# STM32f407.net
KiCad netlist of a schematic drawn in Altium Designer
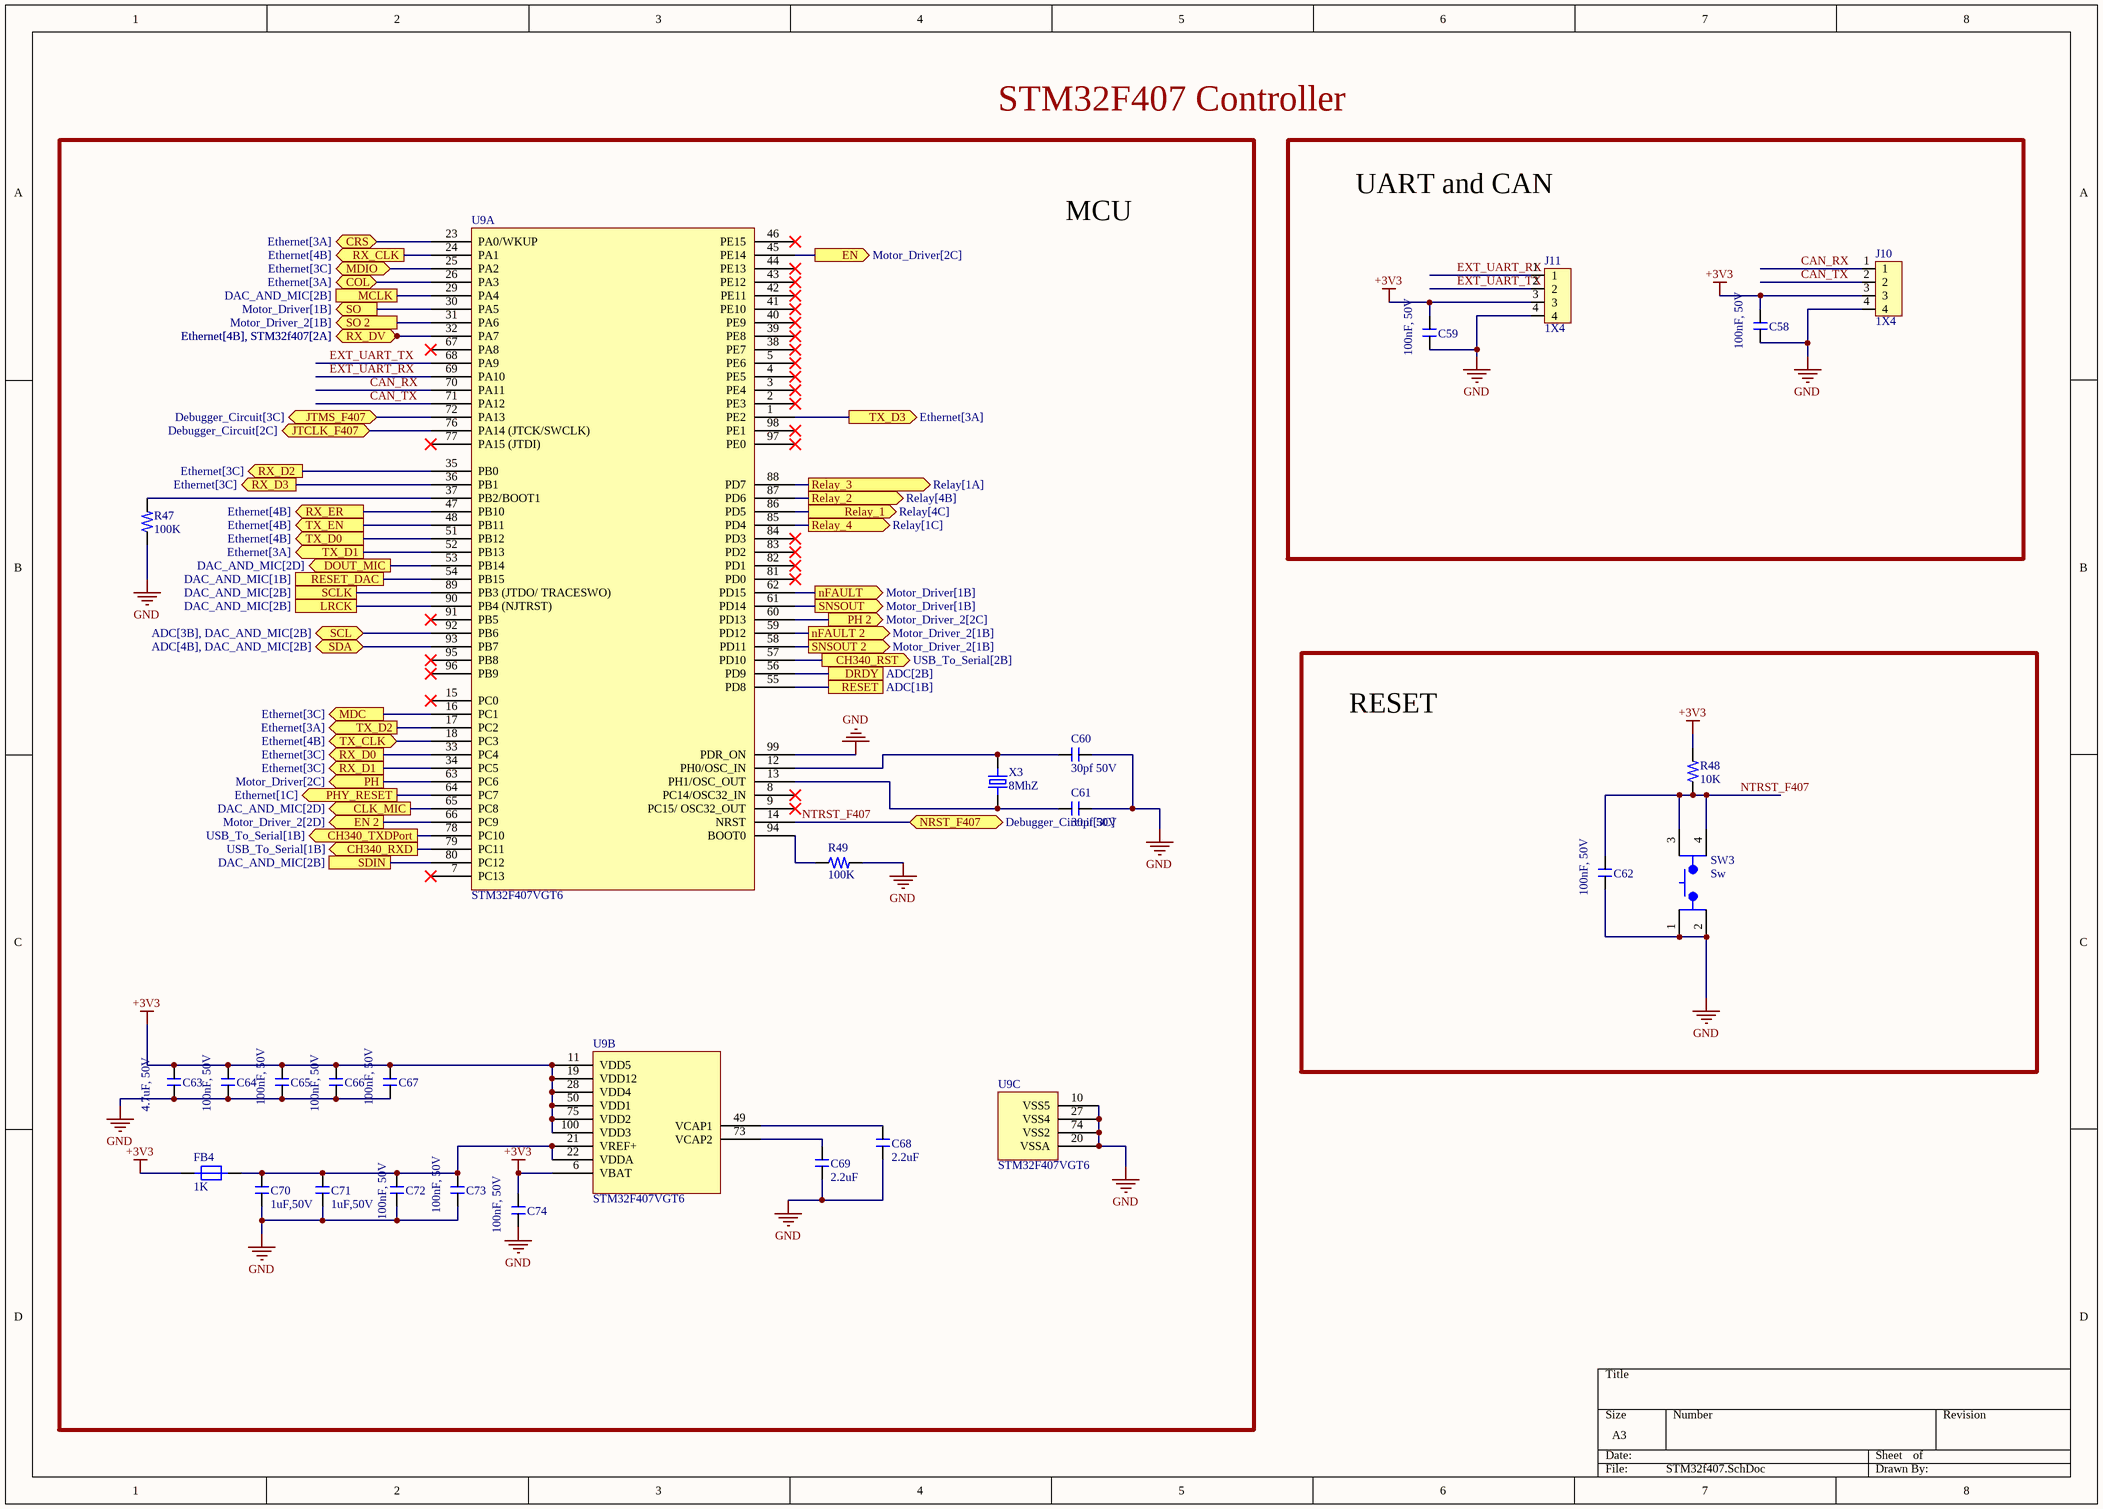
[diagram p0: STM32f407.SchDoc]

(export (version "E")
  (design (tool "Eeschema 10.0.6"))
  (components
    (comp (ref "C58")
      (value "100nF, 50V")
      (footprint "Capacitor_0805")
      (description "Multilayer Ceramic Capacitor, 0.1 uF, 50 V, ï¿½ 10%, X7R, 0805 [2012 Metric]")
      (fields
        (field (name "MANUFACTURER") "Samsung")
        (field (name "MANUFACTURER PART NUMBER") "CL21B104KBCNNNC")
      )
      (libsource (lib "Schematics_Library_Hanif") (part "Cap_100nF_0805"))
    )
    (comp (ref "C59")
      (value "100nF, 50V")
      (footprint "Capacitor_0805")
      (description "Multilayer Ceramic Capacitor, 0.1 uF, 50 V, ï¿½ 10%, X7R, 0805 [2012 Metric]")
      (fields
        (field (name "MANUFACTURER") "Samsung")
        (field (name "MANUFACTURER PART NUMBER") "CL21B104KBCNNNC")
      )
      (libsource (lib "Schematics_Library_Hanif") (part "Cap_100nF_0805"))
    )
    (comp (ref "C60")
      (value "30pf 50V")
      (footprint "Capacitor_0805")
      (fields
        (field (name "MANUFACTURER") "KEMET")
        (field (name "MANUFACTURER PART NUMBER") "C0805C300K5GACTU")
      )
      (libsource (lib "Schematics_Library_Hanif") (part "Cap_30pf_0805"))
    )
    (comp (ref "C61")
      (value "30pf 50V")
      (footprint "Capacitor_0805")
      (fields
        (field (name "MANUFACTURER") "KEMET")
        (field (name "MANUFACTURER PART NUMBER") "C0805C300K5GACTU")
      )
      (libsource (lib "Schematics_Library_Hanif") (part "Cap_30pf_0805"))
    )
    (comp (ref "C62")
      (value "100nF, 50V")
      (footprint "Capacitor_0805")
      (description "Multilayer Ceramic Capacitor, 0.1 uF, 50 V, ï¿½ 10%, X7R, 0805 [2012 Metric]")
      (fields
        (field (name "MANUFACTURER") "Samsung")
        (field (name "MANUFACTURER PART NUMBER") "CL21B104KBCNNNC")
      )
      (libsource (lib "Schematics_Library_Hanif") (part "Cap_100nF_0805"))
    )
    (comp (ref "C63")
      (value "4.7uF, 50V")
      (footprint "Capacitor_0805")
      (description "Multilayer Ceramic Capacitor, 4.7 uF, 50 V, ï¿½ 10%, X5R, 0805 [2012 Metric]")
      (fields
        (field (name "MANUFACTURER") "Murata")
        (field (name "MANUFACTURER PART NUMBER") "GRM21BR61H475KE51L")
      )
      (libsource (lib "Schematics_Library_Hanif") (part "Cap_4.7uF_0805"))
    )
    (comp (ref "C64")
      (value "100nF, 50V")
      (footprint "Capacitor_0805")
      (description "Multilayer Ceramic Capacitor, 0.1 uF, 50 V, ï¿½ 10%, X7R, 0805 [2012 Metric]")
      (fields
        (field (name "MANUFACTURER") "Samsung")
        (field (name "MANUFACTURER PART NUMBER") "CL21B104KBCNNNC")
      )
      (libsource (lib "Schematics_Library_Hanif") (part "Cap_100nF_0805"))
    )
    (comp (ref "C65")
      (value "100nF, 50V")
      (footprint "Capacitor_0805")
      (description "Multilayer Ceramic Capacitor, 0.1 uF, 50 V, ï¿½ 10%, X7R, 0805 [2012 Metric]")
      (fields
        (field (name "MANUFACTURER") "Samsung")
        (field (name "MANUFACTURER PART NUMBER") "CL21B104KBCNNNC")
      )
      (libsource (lib "Schematics_Library_Hanif") (part "Cap_100nF_0805"))
    )
    (comp (ref "C66")
      (value "100nF, 50V")
      (footprint "Capacitor_0805")
      (description "Multilayer Ceramic Capacitor, 0.1 uF, 50 V, ï¿½ 10%, X7R, 0805 [2012 Metric]")
      (fields
        (field (name "MANUFACTURER") "Samsung")
        (field (name "MANUFACTURER PART NUMBER") "CL21B104KBCNNNC")
      )
      (libsource (lib "Schematics_Library_Hanif") (part "Cap_100nF_0805"))
    )
    (comp (ref "C67")
      (value "100nF, 50V")
      (footprint "Capacitor_0805")
      (description "Multilayer Ceramic Capacitor, 0.1 uF, 50 V, ï¿½ 10%, X7R, 0805 [2012 Metric]")
      (fields
        (field (name "MANUFACTURER") "Samsung")
        (field (name "MANUFACTURER PART NUMBER") "CL21B104KBCNNNC")
      )
      (libsource (lib "Schematics_Library_Hanif") (part "Cap_100nF_0805"))
    )
    (comp (ref "C68")
      (value "2.2uF")
      (footprint "Capacitor_0805")
      (description "Multilayer Ceramic Capacitor, 2.2 uF, 25 V, ± 10%, X7R, 0805 [2012 Metric]")
      (fields
        (field (name "MANUFACTURER") "Samsung")
        (field (name "MANUFACTURER PART NUMBER") "CL21B225KAFNFNE")
      )
      (libsource (lib "Schematics_Library_Hanif") (part "CAP_2.2uF_0805"))
    )
    (comp (ref "C69")
      (value "2.2uF")
      (footprint "Capacitor_0805")
      (description "Multilayer Ceramic Capacitor, 2.2 uF, 25 V, ± 10%, X7R, 0805 [2012 Metric]")
      (fields
        (field (name "MANUFACTURER") "Samsung")
        (field (name "MANUFACTURER PART NUMBER") "CL21B225KAFNFNE")
      )
      (libsource (lib "Schematics_Library_Hanif") (part "CAP_2.2uF_0805"))
    )
    (comp (ref "C70")
      (value "1uF,50V")
      (footprint "Capacitor_0805")
      (description "0805 1 uF 50 V ±5 % Tolerance X7R Surface Mount Multilayer Ceramic Capacitor")
      (fields
        (field (name "MANUFACTURER") "Yageo")
        (field (name "MANUFACTURER PART NUMBER") "CC0805JKX7R9BB105")
      )
      (libsource (lib "Schematics_Library_Hanif") (part "Cap_1uF_0805"))
    )
    (comp (ref "C71")
      (value "1uF,50V")
      (footprint "Capacitor_0805")
      (description "0805 1 uF 50 V ±5 % Tolerance X7R Surface Mount Multilayer Ceramic Capacitor")
      (fields
        (field (name "MANUFACTURER") "Yageo")
        (field (name "MANUFACTURER PART NUMBER") "CC0805JKX7R9BB105")
      )
      (libsource (lib "Schematics_Library_Hanif") (part "Cap_1uF_0805"))
    )
    (comp (ref "C72")
      (value "100nF, 50V")
      (footprint "Capacitor_0805")
      (description "Multilayer Ceramic Capacitor, 0.1 uF, 50 V, ï¿½ 10%, X7R, 0805 [2012 Metric]")
      (fields
        (field (name "MANUFACTURER") "Samsung")
        (field (name "MANUFACTURER PART NUMBER") "CL21B104KBCNNNC")
      )
      (libsource (lib "Schematics_Library_Hanif") (part "Cap_100nF_0805"))
    )
    (comp (ref "C73")
      (value "100nF, 50V")
      (footprint "Capacitor_0805")
      (description "Multilayer Ceramic Capacitor, 0.1 uF, 50 V, ï¿½ 10%, X7R, 0805 [2012 Metric]")
      (fields
        (field (name "MANUFACTURER") "Samsung")
        (field (name "MANUFACTURER PART NUMBER") "CL21B104KBCNNNC")
      )
      (libsource (lib "Schematics_Library_Hanif") (part "Cap_100nF_0805"))
    )
    (comp (ref "C74")
      (value "100nF, 50V")
      (footprint "Capacitor_0805")
      (description "Multilayer Ceramic Capacitor, 0.1 uF, 50 V, ï¿½ 10%, X7R, 0805 [2012 Metric]")
      (fields
        (field (name "MANUFACTURER") "Samsung")
        (field (name "MANUFACTURER PART NUMBER") "CL21B104KBCNNNC")
      )
      (libsource (lib "Schematics_Library_Hanif") (part "Cap_100nF_0805"))
    )
    (comp (ref "FB4")
      (value "1K")
      (footprint "FB_0805")
      (description "Ferrite Beads Multi-Layer High Current 1KOhm 25% 100MHz 1.6A 0.12Ohm DCR 0805 Automotive T/R")
      (fields
        (field (name "MANUFACTURER") "Murata")
        (field (name "MANUFACTURER PART NUMBER") "BLM21SP102SH1D")
      )
      (libsource (lib "Schematics_Library_Hanif") (part "FB_BLM21SP102SH1D"))
    )
    (comp (ref "J10")
      (value "1X4")
      (footprint "Header_1X4_2.54mm")
      (description "THT Vertical Pin Header WR-PHD, Pitch 2.54 mm, Single Row, 4 pins")
      (fields
        (field (name "MANUFACTURER") "Wurth Electronics")
        (field (name "MANUFACTURER PART NUMBER") "61300411121")
      )
      (libsource (lib "Schematics_Library_Hanif") (part "Header_Male_1X4_2.54"))
    )
    (comp (ref "J11")
      (value "1X4")
      (footprint "Header_1X4_2.54mm")
      (description "THT Vertical Pin Header WR-PHD, Pitch 2.54 mm, Single Row, 4 pins")
      (fields
        (field (name "MANUFACTURER") "Wurth Electronics")
        (field (name "MANUFACTURER PART NUMBER") "61300411121")
      )
      (libsource (lib "Schematics_Library_Hanif") (part "Header_Male_1X4_2.54"))
    )
    (comp (ref "R47")
      (value "100K")
      (footprint "Resistor_0603")
      (description "Res Thick Film 0603 100K Ohm 1% 0.1W(1/10W) ±100ppm/C Pad SMD Automotive T/R")
      (fields
        (field (name "MANUFACTURER") "Stackpole Electronics")
        (field (name "MANUFACTURER PART NUMBER") "RMCF0603FT100K")
      )
      (libsource (lib "Schematics_Library_Hanif") (part "R_100K_0603"))
    )
    (comp (ref "R48")
      (value "10K")
      (footprint "Resistor_0603")
      (description "SMD Chip Resistor, 10 kOhm, ï¿½ 1%, 100 mW, 0603 [1608 Metric], Thick Film, General Purpose")
      (fields
        (field (name "MANUFACTURER") "Yageo")
        (field (name "MANUFACTURER PART NUMBER") "RC0603FR-0710KL")
      )
      (libsource (lib "Schematics_Library_Hanif") (part "R_10K_0603"))
    )
    (comp (ref "R49")
      (value "100K")
      (footprint "Resistor_0603")
      (description "Res Thick Film 0603 100K Ohm 1% 0.1W(1/10W) ±100ppm/C Pad SMD Automotive T/R")
      (fields
        (field (name "MANUFACTURER") "Stackpole Electronics")
        (field (name "MANUFACTURER PART NUMBER") "RMCF0603FT100K")
      )
      (libsource (lib "Schematics_Library_Hanif") (part "R_100K_0603"))
    )
    (comp (ref "SW3")
      (value "Sw")
      (footprint "SW_Tactile_SMD")
      (description "TL3305A Series SPST 12 V 4.5 x 4.5 mm 260 gf Top Actuated SMT Tactile Switch")
      (fields
        (field (name "MANUFACTURER") "E-Switch")
        (field (name "MANUFACTURER PART NUMBER") "TL3305AF260QG")
      )
      (libsource (lib "Schematics_Library_Hanif") (part "SW_Tactile_SPST"))
    )
    (comp (ref "U9")
      (value "STM32F407VGT6")
      (footprint "QFN100_19.6_669_58X10_SMD")
      (description "ARM® Cortex®-M4 STM32F4 Microcontroller IC 32-Bit 168MHz 1MB (1M x 8) FLASH 100-LQFP (14x14)")
      (fields (field (name "MANUFACTURER") "STMicroelectronics"))
      (libsource (lib "Schematics_Library_Hanif") (part "IC_STM32F407VGT6"))
    )
    (comp (ref "X3")
      (value "8MhZ")
      (footprint "XTAL_8MhZ")
      (description "Crystal 8MHz ±30ppm (Tol) ±50ppm (Stability) 32pF FUND 60Ohm 2-Pin HC-49/USX SMD T/R")
      (fields
        (field (name "MANUFACTURER") "ECS International")
        (field (name "MANUFACTURER PART NUMBER") "ECS-80-32-5PX-TR")
      )
      (libsource (lib "Schematics_Library_Hanif") (part "Xtal_8MHz"))
    )
  )
  (nets
    (net (code "1") (name "+3V3") (class "Default")
      (node (ref "C58") (pin "2") (pinfunction "2_2") (pintype "passive"))
      (node (ref "C59") (pin "2") (pinfunction "2_2") (pintype "passive"))
      (node (ref "C63") (pin "2") (pinfunction "2_2") (pintype "passive"))
      (node (ref "C64") (pin "2") (pinfunction "2_2") (pintype "passive"))
      (node (ref "C65") (pin "2") (pinfunction "2_2") (pintype "passive"))
      (node (ref "C66") (pin "2") (pinfunction "2_2") (pintype "passive"))
      (node (ref "C67") (pin "2") (pinfunction "2_2") (pintype "passive"))
      (node (ref "C74") (pin "2") (pinfunction "2_2") (pintype "passive"))
      (node (ref "FB4") (pin "1") (pinfunction "1_1") (pintype "passive"))
      (node (ref "J10") (pin "3") (pinfunction "3_3") (pintype "passive"))
      (node (ref "J11") (pin "3") (pinfunction "3_3") (pintype "passive"))
      (node (ref "R48") (pin "2") (pinfunction "2_2") (pintype "passive"))
      (node (ref "U9") (pin "100") (pinfunction "VDD3_100") (pintype "passive"))
      (node (ref "U9") (pin "11") (pinfunction "VDD5_11") (pintype "passive"))
      (node (ref "U9") (pin "19") (pinfunction "VDD12_19") (pintype "passive"))
      (node (ref "U9") (pin "28") (pinfunction "VDD4_28") (pintype "passive"))
      (node (ref "U9") (pin "50") (pinfunction "VDD1_50") (pintype "passive"))
      (node (ref "U9") (pin "6") (pinfunction "VBAT_6") (pintype "passive"))
      (node (ref "U9") (pin "75") (pinfunction "VDD2_75") (pintype "passive"))
    )
    (net (code "2") (name "/CAN_RX") (class "Default")
      (node (ref "J10") (pin "1") (pinfunction "1_1") (pintype "passive"))
      (node (ref "U9") (pin "70") (pinfunction "PA11_70") (pintype "passive"))
    )
    (net (code "3") (name "/CAN_TX") (class "Default")
      (node (ref "J10") (pin "2") (pinfunction "2_2") (pintype "passive"))
      (node (ref "U9") (pin "71") (pinfunction "PA12_71") (pintype "passive"))
    )
    (net (code "4") (name "/CH340_RST") (class "Default")
      (node (ref "U9") (pin "57") (pinfunction "PD10_57") (pintype "passive"))
    )
    (net (code "5") (name "/CH340_RXD") (class "Default")
      (node (ref "U9") (pin "79") (pinfunction "PC11_79") (pintype "passive"))
    )
    (net (code "6") (name "/CH340_TXDPort") (class "Default")
      (node (ref "U9") (pin "78") (pinfunction "PC10_78") (pintype "passive"))
    )
    (net (code "7") (name "/CLK_MIC") (class "Default")
      (node (ref "U9") (pin "65") (pinfunction "PC8_65") (pintype "passive"))
    )
    (net (code "8") (name "/COL") (class "Default")
      (node (ref "U9") (pin "26") (pinfunction "PA3_26") (pintype "passive"))
    )
    (net (code "9") (name "/CRS") (class "Default")
      (node (ref "U9") (pin "23") (pinfunction "PA0/WKUP_23") (pintype "passive"))
    )
    (net (code "10") (name "/DOUT_MIC") (class "Default")
      (node (ref "U9") (pin "53") (pinfunction "PB14_53") (pintype "passive"))
    )
    (net (code "11") (name "/DRDY") (class "Default")
      (node (ref "U9") (pin "56") (pinfunction "PD9_56") (pintype "passive"))
    )
    (net (code "12") (name "/EN") (class "Default")
      (node (ref "U9") (pin "45") (pinfunction "PE14_45") (pintype "passive"))
    )
    (net (code "13") (name "/EN 2") (class "Default")
      (node (ref "U9") (pin "66") (pinfunction "PC9_66") (pintype "passive"))
    )
    (net (code "14") (name "/EXT_UART_RX") (class "Default")
      (node (ref "J11") (pin "1") (pinfunction "1_1") (pintype "passive"))
      (node (ref "U9") (pin "69") (pinfunction "PA10_69") (pintype "passive"))
    )
    (net (code "15") (name "/EXT_UART_TX") (class "Default")
      (node (ref "J11") (pin "2") (pinfunction "2_2") (pintype "passive"))
      (node (ref "U9") (pin "68") (pinfunction "PA9_68") (pintype "passive"))
    )
    (net (code "16") (name "/JTCLK_F407") (class "Default")
      (node (ref "U9") (pin "76") (pinfunction "PA14_(JTCK/SWCLK)_76") (pintype "passive"))
    )
    (net (code "17") (name "/JTMS_F407") (class "Default")
      (node (ref "U9") (pin "72") (pinfunction "PA13_72") (pintype "passive"))
    )
    (net (code "18") (name "/LRCK") (class "Default")
      (node (ref "U9") (pin "90") (pinfunction "PB4_(NJTRST)_90") (pintype "passive"))
    )
    (net (code "19") (name "/MCLK") (class "Default")
      (node (ref "U9") (pin "29") (pinfunction "PA4_29") (pintype "passive"))
    )
    (net (code "20") (name "/MDC") (class "Default")
      (node (ref "U9") (pin "16") (pinfunction "PC1_16") (pintype "passive"))
    )
    (net (code "21") (name "/MDIO") (class "Default")
      (node (ref "U9") (pin "25") (pinfunction "PA2_25") (pintype "passive"))
    )
    (net (code "22") (name "/NTRST_F407") (class "Default")
      (node (ref "C62") (pin "2") (pinfunction "2_2") (pintype "passive"))
      (node (ref "R48") (pin "1") (pinfunction "1_1") (pintype "passive"))
      (node (ref "SW3") (pin "3") (pinfunction "3_3") (pintype "passive"))
      (node (ref "SW3") (pin "4") (pinfunction "4_4") (pintype "passive"))
      (node (ref "U9") (pin "14") (pinfunction "NRST_14") (pintype "passive"))
    )
    (net (code "23") (name "/PH") (class "Default")
      (node (ref "U9") (pin "63") (pinfunction "PC6_63") (pintype "passive"))
    )
    (net (code "24") (name "/PH 2") (class "Default")
      (node (ref "U9") (pin "60") (pinfunction "PD13_60") (pintype "passive"))
    )
    (net (code "25") (name "/PHY_RESET") (class "Default")
      (node (ref "U9") (pin "64") (pinfunction "PC7_64") (pintype "passive"))
    )
    (net (code "26") (name "/RESET") (class "Default")
      (node (ref "U9") (pin "55") (pinfunction "PD8_55") (pintype "passive"))
    )
    (net (code "27") (name "/RESET_DAC") (class "Default")
      (node (ref "U9") (pin "54") (pinfunction "PB15_54") (pintype "passive"))
    )
    (net (code "28") (name "/RX_CLK") (class "Default")
      (node (ref "U9") (pin "24") (pinfunction "PA1_24") (pintype "passive"))
    )
    (net (code "29") (name "/RX_D0") (class "Default")
      (node (ref "U9") (pin "33") (pinfunction "PC4_33") (pintype "passive"))
    )
    (net (code "30") (name "/RX_D1") (class "Default")
      (node (ref "U9") (pin "34") (pinfunction "PC5_34") (pintype "passive"))
    )
    (net (code "31") (name "/RX_D2") (class "Default")
      (node (ref "U9") (pin "35") (pinfunction "PB0_35") (pintype "passive"))
    )
    (net (code "32") (name "/RX_D3") (class "Default")
      (node (ref "U9") (pin "36") (pinfunction "PB1_36") (pintype "passive"))
    )
    (net (code "33") (name "/RX_DV") (class "Default")
      (node (ref "U9") (pin "32") (pinfunction "PA7_32") (pintype "passive"))
    )
    (net (code "34") (name "/RX_ER") (class "Default")
      (node (ref "U9") (pin "47") (pinfunction "PB10_47") (pintype "passive"))
    )
    (net (code "35") (name "/Relay_1") (class "Default")
      (node (ref "U9") (pin "86") (pinfunction "PD5_86") (pintype "passive"))
    )
    (net (code "36") (name "/Relay_2") (class "Default")
      (node (ref "U9") (pin "87") (pinfunction "PD6_87") (pintype "passive"))
    )
    (net (code "37") (name "/Relay_3") (class "Default")
      (node (ref "U9") (pin "88") (pinfunction "PD7_88") (pintype "passive"))
    )
    (net (code "38") (name "/Relay_4") (class "Default")
      (node (ref "U9") (pin "85") (pinfunction "PD4_85") (pintype "passive"))
    )
    (net (code "39") (name "/SCL") (class "Default")
      (node (ref "U9") (pin "92") (pinfunction "PB6_92") (pintype "passive"))
    )
    (net (code "40") (name "/SCLK") (class "Default")
      (node (ref "U9") (pin "89") (pinfunction "PB3_(JTDO/_TRACESWO)_89") (pintype "passive"))
    )
    (net (code "41") (name "/SDA") (class "Default")
      (node (ref "U9") (pin "93") (pinfunction "PB7_93") (pintype "passive"))
    )
    (net (code "42") (name "/SDIN") (class "Default")
      (node (ref "U9") (pin "80") (pinfunction "PC12_80") (pintype "passive"))
    )
    (net (code "43") (name "/SNSOUT") (class "Default")
      (node (ref "U9") (pin "61") (pinfunction "PD14_61") (pintype "passive"))
    )
    (net (code "44") (name "/SNSOUT 2") (class "Default")
      (node (ref "U9") (pin "58") (pinfunction "PD11_58") (pintype "passive"))
    )
    (net (code "45") (name "/SO") (class "Default")
      (node (ref "U9") (pin "30") (pinfunction "PA5_30") (pintype "passive"))
    )
    (net (code "46") (name "/SO 2") (class "Default")
      (node (ref "U9") (pin "31") (pinfunction "PA6_31") (pintype "passive"))
    )
    (net (code "47") (name "/TX_CLK") (class "Default")
      (node (ref "U9") (pin "18") (pinfunction "PC3_18") (pintype "passive"))
    )
    (net (code "48") (name "/TX_D0") (class "Default")
      (node (ref "U9") (pin "51") (pinfunction "PB12_51") (pintype "passive"))
    )
    (net (code "49") (name "/TX_D1") (class "Default")
      (node (ref "U9") (pin "52") (pinfunction "PB13_52") (pintype "passive"))
    )
    (net (code "50") (name "/TX_D2") (class "Default")
      (node (ref "U9") (pin "17") (pinfunction "PC2_17") (pintype "passive"))
    )
    (net (code "51") (name "/TX_D3") (class "Default")
      (node (ref "U9") (pin "1") (pinfunction "PE2_1") (pintype "passive"))
    )
    (net (code "52") (name "/TX_EN") (class "Default")
      (node (ref "U9") (pin "48") (pinfunction "PB11_48") (pintype "passive"))
    )
    (net (code "53") (name "/nFAULT") (class "Default")
      (node (ref "U9") (pin "62") (pinfunction "PD15_62") (pintype "passive"))
    )
    (net (code "54") (name "/nFAULT 2") (class "Default")
      (node (ref "U9") (pin "59") (pinfunction "PD12_59") (pintype "passive"))
    )
    (net (code "55") (name "GND") (class "Default")
      (node (ref "C58") (pin "1") (pinfunction "1_1") (pintype "passive"))
      (node (ref "C59") (pin "1") (pinfunction "1_1") (pintype "passive"))
      (node (ref "C60") (pin "1") (pinfunction "1_1") (pintype "passive"))
      (node (ref "C61") (pin "1") (pinfunction "1_1") (pintype "passive"))
      (node (ref "C62") (pin "1") (pinfunction "1_1") (pintype "passive"))
      (node (ref "C63") (pin "1") (pinfunction "1_1") (pintype "passive"))
      (node (ref "C64") (pin "1") (pinfunction "1_1") (pintype "passive"))
      (node (ref "C65") (pin "1") (pinfunction "1_1") (pintype "passive"))
      (node (ref "C66") (pin "1") (pinfunction "1_1") (pintype "passive"))
      (node (ref "C67") (pin "1") (pinfunction "1_1") (pintype "passive"))
      (node (ref "C68") (pin "1") (pinfunction "1_1") (pintype "passive"))
      (node (ref "C69") (pin "1") (pinfunction "1_1") (pintype "passive"))
      (node (ref "C70") (pin "1") (pinfunction "1_1") (pintype "passive"))
      (node (ref "C71") (pin "1") (pinfunction "1_1") (pintype "passive"))
      (node (ref "C72") (pin "1") (pinfunction "1_1") (pintype "passive"))
      (node (ref "C73") (pin "1") (pinfunction "1_1") (pintype "passive"))
      (node (ref "C74") (pin "1") (pinfunction "1_1") (pintype "passive"))
      (node (ref "J10") (pin "4") (pinfunction "4_4") (pintype "passive"))
      (node (ref "J11") (pin "4") (pinfunction "4_4") (pintype "passive"))
      (node (ref "R47") (pin "1") (pinfunction "1_1") (pintype "passive"))
      (node (ref "R49") (pin "2") (pinfunction "2_2") (pintype "passive"))
      (node (ref "SW3") (pin "1") (pinfunction "1_1") (pintype "passive"))
      (node (ref "SW3") (pin "2") (pinfunction "2_2") (pintype "passive"))
      (node (ref "U9") (pin "10") (pinfunction "VSS5_10") (pintype "passive"))
      (node (ref "U9") (pin "20") (pinfunction "VSSA_20") (pintype "passive"))
      (node (ref "U9") (pin "27") (pinfunction "VSS4_27") (pintype "passive"))
      (node (ref "U9") (pin "74") (pinfunction "VSS2_74") (pintype "passive"))
      (node (ref "U9") (pin "99") (pinfunction "PDR_ON_99") (pintype "passive"))
    )
    (net (code "56") (name "Net-(U9A-BOOT0)") (class "Default")
      (node (ref "R49") (pin "1") (pinfunction "1_1") (pintype "passive"))
      (node (ref "U9") (pin "94") (pinfunction "BOOT0_94") (pintype "passive"))
    )
    (net (code "57") (name "Net-(U9A-PB2{slash}BOOT1)") (class "Default")
      (node (ref "R47") (pin "2") (pinfunction "2_2") (pintype "passive"))
      (node (ref "U9") (pin "37") (pinfunction "PB2/BOOT1_37") (pintype "passive"))
    )
    (net (code "58") (name "Net-(U9A-PH0{slash}OSC_IN)") (class "Default")
      (node (ref "C60") (pin "2") (pinfunction "2_2") (pintype "passive"))
      (node (ref "U9") (pin "12") (pinfunction "PH0/OSC_IN_12") (pintype "passive"))
      (node (ref "X3") (pin "2") (pinfunction "2_2") (pintype "passive"))
    )
    (net (code "59") (name "Net-(U9A-PH1{slash}OSC_OUT)") (class "Default")
      (node (ref "C61") (pin "2") (pinfunction "2_2") (pintype "passive"))
      (node (ref "U9") (pin "13") (pinfunction "PH1/OSC_OUT_13") (pintype "passive"))
      (node (ref "X3") (pin "1") (pinfunction "1_1") (pintype "passive"))
    )
    (net (code "60") (name "Net-(U9B-VCAP1)") (class "Default")
      (node (ref "C68") (pin "2") (pinfunction "2_2") (pintype "passive"))
      (node (ref "U9") (pin "49") (pinfunction "VCAP1_49") (pintype "passive"))
    )
    (net (code "61") (name "Net-(U9B-VCAP2)") (class "Default")
      (node (ref "C69") (pin "2") (pinfunction "2_2") (pintype "passive"))
      (node (ref "U9") (pin "73") (pinfunction "VCAP2_73") (pintype "passive"))
    )
    (net (code "62") (name "Net-(U9B-VDDA)") (class "Default")
      (node (ref "C70") (pin "2") (pinfunction "2_2") (pintype "passive"))
      (node (ref "C71") (pin "2") (pinfunction "2_2") (pintype "passive"))
      (node (ref "C72") (pin "2") (pinfunction "2_2") (pintype "passive"))
      (node (ref "C73") (pin "2") (pinfunction "2_2") (pintype "passive"))
      (node (ref "FB4") (pin "2") (pinfunction "2_2") (pintype "passive"))
      (node (ref "U9") (pin "21") (pinfunction "VREF+_21") (pintype "passive"))
      (node (ref "U9") (pin "22") (pinfunction "VDDA_22") (pintype "passive"))
    )
    (net (code "63") (name "unconnected-(U9A-PA8-Pad67)") (class "Default")
      (node (ref "U9") (pin "67") (pinfunction "PA8_67") (pintype "passive+no_connect"))
    )
    (net (code "64") (name "unconnected-(U9A-PA15_(JTDI)-Pad77)") (class "Default")
      (node (ref "U9") (pin "77") (pinfunction "PA15_(JTDI)_77") (pintype "passive+no_connect"))
    )
    (net (code "65") (name "unconnected-(U9A-PB5-Pad91)") (class "Default")
      (node (ref "U9") (pin "91") (pinfunction "PB5_91") (pintype "passive+no_connect"))
    )
    (net (code "66") (name "unconnected-(U9A-PB8-Pad95)") (class "Default")
      (node (ref "U9") (pin "95") (pinfunction "PB8_95") (pintype "passive+no_connect"))
    )
    (net (code "67") (name "unconnected-(U9A-PB9-Pad96)") (class "Default")
      (node (ref "U9") (pin "96") (pinfunction "PB9_96") (pintype "passive+no_connect"))
    )
    (net (code "68") (name "unconnected-(U9A-PC0-Pad15)") (class "Default")
      (node (ref "U9") (pin "15") (pinfunction "PC0_15") (pintype "passive+no_connect"))
    )
    (net (code "69") (name "unconnected-(U9A-PC13-Pad7)") (class "Default")
      (node (ref "U9") (pin "7") (pinfunction "PC13_7") (pintype "passive+no_connect"))
    )
    (net (code "70") (name "unconnected-(U9A-PC14{slash}OSC32_IN-Pad8)") (class "Default")
      (node (ref "U9") (pin "8") (pinfunction "PC14/OSC32_IN_8") (pintype "passive+no_connect"))
    )
    (net (code "71") (name "unconnected-(U9A-PC15{slash}_OSC32_OUT-Pad9)") (class "Default")
      (node (ref "U9") (pin "9") (pinfunction "PC15/_OSC32_OUT_9") (pintype "passive+no_connect"))
    )
    (net (code "72") (name "unconnected-(U9A-PD0-Pad81)") (class "Default")
      (node (ref "U9") (pin "81") (pinfunction "PD0_81") (pintype "passive+no_connect"))
    )
    (net (code "73") (name "unconnected-(U9A-PD1-Pad82)") (class "Default")
      (node (ref "U9") (pin "82") (pinfunction "PD1_82") (pintype "passive+no_connect"))
    )
    (net (code "74") (name "unconnected-(U9A-PD2-Pad83)") (class "Default")
      (node (ref "U9") (pin "83") (pinfunction "PD2_83") (pintype "passive+no_connect"))
    )
    (net (code "75") (name "unconnected-(U9A-PD3-Pad84)") (class "Default")
      (node (ref "U9") (pin "84") (pinfunction "PD3_84") (pintype "passive+no_connect"))
    )
    (net (code "76") (name "unconnected-(U9A-PE0-Pad97)") (class "Default")
      (node (ref "U9") (pin "97") (pinfunction "PE0_97") (pintype "passive+no_connect"))
    )
    (net (code "77") (name "unconnected-(U9A-PE1-Pad98)") (class "Default")
      (node (ref "U9") (pin "98") (pinfunction "PE1_98") (pintype "passive+no_connect"))
    )
    (net (code "78") (name "unconnected-(U9A-PE3-Pad2)") (class "Default")
      (node (ref "U9") (pin "2") (pinfunction "PE3_2") (pintype "passive+no_connect"))
    )
    (net (code "79") (name "unconnected-(U9A-PE4-Pad3)") (class "Default")
      (node (ref "U9") (pin "3") (pinfunction "PE4_3") (pintype "passive+no_connect"))
    )
    (net (code "80") (name "unconnected-(U9A-PE5-Pad4)") (class "Default")
      (node (ref "U9") (pin "4") (pinfunction "PE5_4") (pintype "passive+no_connect"))
    )
    (net (code "81") (name "unconnected-(U9A-PE6-Pad5)") (class "Default")
      (node (ref "U9") (pin "5") (pinfunction "PE6_5") (pintype "passive+no_connect"))
    )
    (net (code "82") (name "unconnected-(U9A-PE7-Pad38)") (class "Default")
      (node (ref "U9") (pin "38") (pinfunction "PE7_38") (pintype "passive+no_connect"))
    )
    (net (code "83") (name "unconnected-(U9A-PE8-Pad39)") (class "Default")
      (node (ref "U9") (pin "39") (pinfunction "PE8_39") (pintype "passive+no_connect"))
    )
    (net (code "84") (name "unconnected-(U9A-PE9-Pad40)") (class "Default")
      (node (ref "U9") (pin "40") (pinfunction "PE9_40") (pintype "passive+no_connect"))
    )
    (net (code "85") (name "unconnected-(U9A-PE10-Pad41)") (class "Default")
      (node (ref "U9") (pin "41") (pinfunction "PE10_41") (pintype "passive+no_connect"))
    )
    (net (code "86") (name "unconnected-(U9A-PE11-Pad42)") (class "Default")
      (node (ref "U9") (pin "42") (pinfunction "PE11_42") (pintype "passive+no_connect"))
    )
    (net (code "87") (name "unconnected-(U9A-PE12-Pad43)") (class "Default")
      (node (ref "U9") (pin "43") (pinfunction "PE12_43") (pintype "passive+no_connect"))
    )
    (net (code "88") (name "unconnected-(U9A-PE13-Pad44)") (class "Default")
      (node (ref "U9") (pin "44") (pinfunction "PE13_44") (pintype "passive+no_connect"))
    )
    (net (code "89") (name "unconnected-(U9A-PE15-Pad46)") (class "Default")
      (node (ref "U9") (pin "46") (pinfunction "PE15_46") (pintype "passive+no_connect"))
    )
  )
)
